# Power.net
KiCad netlist of a schematic drawn in Altium Designer
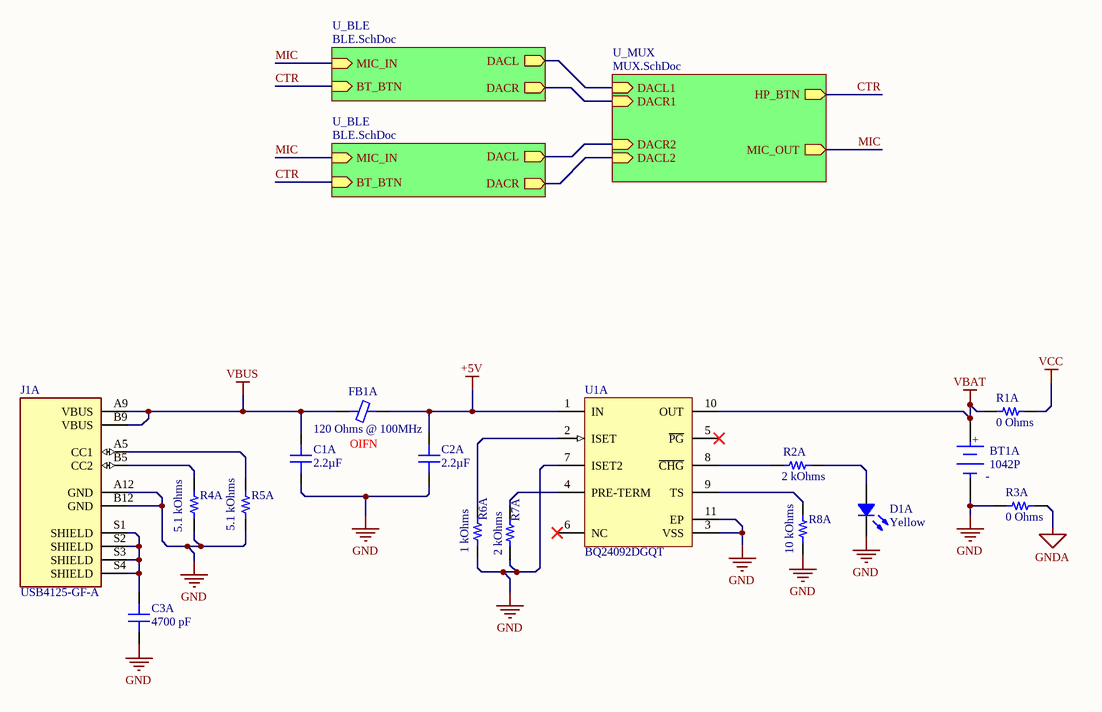
[diagram p0: Power.SchDoc]

(export (version "E")
  (design (tool "Eeschema 10.0.6"))
  (components
    (comp (ref "BT1A")
      (value "1042P")
      (footprint "FP-1042P-MFG")
      (description "BATTERY HOLDER 18650 SMD TAB")
      (libsource (lib "Altium Content Vault") (part "60d3b5b901a8747834971d0eb8cf3fd"))
    )
    (comp (ref "C1A")
      (value "2.2µF")
      (footprint "CAP 0402_1005")
      (description "CAP CER 2.2UF 10V X5R 0402")
      (fields (field (name "PART NUMBER") "0402ZD225KAT2A") (field (name "MANUFACTURER") "AVX Corporation"))
      (libsource (lib "Postgres Altium Library - altium_library") (part "Capacitor"))
    )
    (comp (ref "C2A")
      (value "2.2µF")
      (footprint "CAP 0402_1005")
      (description "CAP CER 2.2UF 10V X5R 0402")
      (fields (field (name "PART NUMBER") "0402ZD225KAT2A") (field (name "MANUFACTURER") "AVX Corporation"))
      (libsource (lib "Postgres Altium Library - altium_library") (part "Capacitor"))
    )
    (comp (ref "C3A")
      (value "4700 pF")
      (footprint "CAP 0402_1005")
      (description "CAP CER 0402 4.7NF 16V X7R 10%")
      (fields (field (name "PART NUMBER") "C0402C472K4RECAUTO") (field (name "MANUFACTURER") "KEMET"))
      (libsource (lib "Postgres Altium Library - altium_library") (part "Capacitor"))
    )
    (comp (ref "D1A")
      (value "Yellow")
      (footprint "LED 0402_1005 YELLOW")
      (description "LED YELLOW CLEAR CHIP SMD")
      (fields (field (name "PART NUMBER") "XZMYK68W-2") (field (name "MANUFACTURER") "SunLED"))
      (libsource (lib "Postgres Altium Library - altium_library") (part "LED"))
    )
    (comp (ref "FB1A")
      (value "120 Ohms @ 100MHz")
      (footprint "FER 0201_0603")
      (description "FERRITE BEAD 120 OHM 0201 1LN")
      (fields (field (name "PART NUMBER") "BKP0603HM121-T") (field (name "MANUFACTURER") "Taiyo Yuden"))
      (libsource (lib "Postgres Altium Library - altium_library") (part "Ferrite Chip"))
    )
    (comp (ref "J1A")
      (value "USB4125-GF-A")
      (footprint "USB4125-GF-A")
      (description "CONN RCPT TYPE C 6P SMD RA")
      (fields (field (name "MP") "USB4125-GF-A_REVA2") (field (name "MANUFACTURER") "GCT"))
      (libsource (lib "Postgres Altium Library - altium_library") (part "USB 3.0 TYPE C 6PIN"))
    )
    (comp (ref "R1A")
      (value "0 Ohms")
      (footprint "RES 0603_1608")
      (description "RCC0603 0R0 ET1 E3")
      (fields (field (name "PART NUMBER") "RCC06030000Z0EA") (field (name "TOLERANCE") "Jumper"))
      (libsource (lib "Postgres Altium Library - altium_library") (part "Resistor"))
    )
    (comp (ref "R2A")
      (value "2 kOhms")
      (footprint "RES 0402_1005")
      (description "RES 2K OHM 1% 1/8W 0402")
      (fields (field (name "PART NUMBER") "AC0402FR-7W2KL") (field (name "TOLERANCE") "±1%"))
      (libsource (lib "Postgres Altium Library - altium_library") (part "Resistor"))
    )
    (comp (ref "R3A")
      (value "0 Ohms")
      (footprint "RES 0603_1608")
      (description "RCC0603 0R0 ET1 E3")
      (fields (field (name "PART NUMBER") "RCC06030000Z0EA") (field (name "TOLERANCE") "Jumper"))
      (libsource (lib "Postgres Altium Library - altium_library") (part "Resistor"))
    )
    (comp (ref "R4A")
      (value "5.1 kOhms")
      (footprint "RES 0402_1005")
      (description "RES SMD 5.1K OHM 1% 1/16W 0402")
      (fields (field (name "PART NUMBER") "AC0402FR-075K1L") (field (name "TOLERANCE") "±1%"))
      (libsource (lib "Postgres Altium Library - altium_library") (part "Resistor"))
    )
    (comp (ref "R5A")
      (value "5.1 kOhms")
      (footprint "RES 0402_1005")
      (description "RES SMD 5.1K OHM 1% 1/16W 0402")
      (fields (field (name "PART NUMBER") "AC0402FR-075K1L") (field (name "TOLERANCE") "±1%"))
      (libsource (lib "Postgres Altium Library - altium_library") (part "Resistor"))
    )
    (comp (ref "R6A")
      (value "1 kOhms")
      (footprint "RES 0402_1005")
      (description "RES SMD 1K OHM 1% 1/16W 0402")
      (fields (field (name "PART NUMBER") "AC0402FR-071KL") (field (name "TOLERANCE") "±1%"))
      (libsource (lib "Postgres Altium Library - altium_library") (part "Resistor"))
    )
    (comp (ref "R7A")
      (value "2 kOhms")
      (footprint "RES 0402_1005")
      (description "RES 2K OHM 1% 1/8W 0402")
      (fields (field (name "PART NUMBER") "AC0402FR-7W2KL") (field (name "TOLERANCE") "±1%"))
      (libsource (lib "Postgres Altium Library - altium_library") (part "Resistor"))
    )
    (comp (ref "R8A")
      (value "10 kOhms")
      (footprint "RES 0402_1005")
      (description "RES SMD 10K OHM 1% 1/16W 0402")
      (fields (field (name "PART NUMBER") "AC0402FR-0710KL") (field (name "TOLERANCE") "±1%"))
      (libsource (lib "Postgres Altium Library - altium_library") (part "Resistor"))
    )
    (comp (ref "U1A")
      (value "BQ24092DGQT")
      (footprint "DGQ0010D_L")
      (fields (field (name "MANUFACTURER") "Texas Instruments"))
      (libsource (lib "Altium Content Vault") (part "TI-BQ24092DGQ10-1675X1445TP"))
    )
  )
  (nets
    (net (code "1") (name "+5V") (class "Default")
      (node (ref "C2A") (pin "2") (pinfunction "2_2") (pintype "passive"))
      (node (ref "FB1A") (pin "2") (pinfunction "2_2") (pintype "passive"))
      (node (ref "U1A") (pin "1") (pinfunction "IN_1") (pintype "power_in"))
    )
    (net (code "8") (name "GND") (class "Default")
      (node (ref "BT1A") (pin "1") (pinfunction "C_1") (pintype "power_in"))
      (node (ref "C1A") (pin "1") (pinfunction "1_1") (pintype "passive"))
      (node (ref "C2A") (pin "1") (pinfunction "1_1") (pintype "passive"))
      (node (ref "C3A") (pin "1") (pinfunction "1_1") (pintype "passive"))
      (node (ref "D1A") (pin "2") (pinfunction "2_2") (pintype "passive"))
      (node (ref "J1A") (pin "A12") (pinfunction "GND_A12") (pintype "power_in"))
      (node (ref "J1A") (pin "B12") (pinfunction "GND_B12") (pintype "power_in"))
      (node (ref "R3A") (pin "1") (pinfunction "1_1") (pintype "passive"))
      (node (ref "R4A") (pin "1") (pinfunction "1_1") (pintype "passive"))
      (node (ref "R5A") (pin "1") (pinfunction "1_1") (pintype "passive"))
      (node (ref "R6A") (pin "1") (pinfunction "1_1") (pintype "passive"))
      (node (ref "R7A") (pin "1") (pinfunction "1_1") (pintype "passive"))
      (node (ref "R8A") (pin "1") (pinfunction "1_1") (pintype "passive"))
      (node (ref "U1A") (pin "11") (pinfunction "EP_11") (pintype "power_in"))
      (node (ref "U1A") (pin "3") (pinfunction "VSS_3") (pintype "power_in"))
      (node (ref "U1A") (pin "7") (pinfunction "ISET2_7") (pintype "passive"))
    )
    (net (code "9") (name "GNDA") (class "Default")
      (node (ref "R3A") (pin "2") (pinfunction "2_2") (pintype "passive"))
    )
    (net (code "10") (name "Net-(C3A-Pad2)") (class "Default")
      (node (ref "C3A") (pin "2") (pinfunction "2_2") (pintype "passive"))
      (node (ref "J1A") (pin "S1") (pinfunction "SHIELD_S1") (pintype "passive"))
      (node (ref "J1A") (pin "S2") (pinfunction "SHIELD_S2") (pintype "passive"))
      (node (ref "J1A") (pin "S3") (pinfunction "SHIELD_S3") (pintype "passive"))
      (node (ref "J1A") (pin "S4") (pinfunction "SHIELD_S4") (pintype "passive"))
    )
    (net (code "11") (name "Net-(D1A-Pad1)") (class "Default")
      (node (ref "D1A") (pin "1") (pinfunction "1_1") (pintype "passive"))
      (node (ref "R2A") (pin "1") (pinfunction "1_1") (pintype "passive"))
    )
    (net (code "12") (name "Net-(J1A-CC1)") (class "Default")
      (node (ref "J1A") (pin "A5") (pinfunction "CC1_A5") (pintype "bidirectional"))
      (node (ref "R5A") (pin "2") (pinfunction "2_2") (pintype "passive"))
    )
    (net (code "13") (name "Net-(J1A-CC2)") (class "Default")
      (node (ref "J1A") (pin "B5") (pinfunction "CC2_B5") (pintype "bidirectional"))
      (node (ref "R4A") (pin "2") (pinfunction "2_2") (pintype "passive"))
    )
    (net (code "14") (name "Net-(U1A-ISET)") (class "Default")
      (node (ref "R6A") (pin "2") (pinfunction "2_2") (pintype "passive"))
      (node (ref "U1A") (pin "2") (pinfunction "ISET_2") (pintype "input"))
    )
    (net (code "15") (name "Net-(U1A-PRE-TERM)") (class "Default")
      (node (ref "R7A") (pin "2") (pinfunction "2_2") (pintype "passive"))
      (node (ref "U1A") (pin "4") (pinfunction "PRE-TERM_4") (pintype "passive"))
    )
    (net (code "16") (name "Net-(U1A-TS)") (class "Default")
      (node (ref "R8A") (pin "2") (pinfunction "2_2") (pintype "passive"))
      (node (ref "U1A") (pin "9") (pinfunction "TS_9") (pintype "passive"))
    )
    (net (code "17") (name "Net-(U1A-~{CHG})") (class "Default")
      (node (ref "R2A") (pin "2") (pinfunction "2_2") (pintype "passive"))
      (node (ref "U1A") (pin "8") (pinfunction "~{CHG}_8") (pintype "tri_state"))
    )
    (net (code "18") (name "VBAT") (class "Default")
      (node (ref "BT1A") (pin "2") (pinfunction "A_2") (pintype "power_in"))
      (node (ref "R1A") (pin "1") (pinfunction "1_1") (pintype "passive"))
      (node (ref "U1A") (pin "10") (pinfunction "OUT_10") (pintype "power_in"))
    )
    (net (code "19") (name "VBUS") (class "Default")
      (node (ref "C1A") (pin "2") (pinfunction "2_2") (pintype "passive"))
      (node (ref "FB1A") (pin "1") (pinfunction "1_1") (pintype "passive"))
      (node (ref "J1A") (pin "A9") (pinfunction "VBUS_A9") (pintype "power_in"))
      (node (ref "J1A") (pin "B9") (pinfunction "VBUS_B9") (pintype "power_in"))
    )
    (net (code "20") (name "VCC") (class "Default")
      (node (ref "R1A") (pin "2") (pinfunction "2_2") (pintype "passive"))
    )
    (net (code "21") (name "unconnected-(U1A-NC-Pad6)") (class "Default")
      (node (ref "U1A") (pin "6") (pinfunction "NC_6") (pintype "passive+no_connect"))
    )
    (net (code "22") (name "unconnected-(U1A-~{PG}-Pad5)") (class "Default")
      (node (ref "U1A") (pin "5") (pinfunction "~{PG}_5") (pintype "tri_state+no_connect"))
    )
  )
)
